# Peripherals.net
KiCad netlist of a schematic drawn in Altium Designer
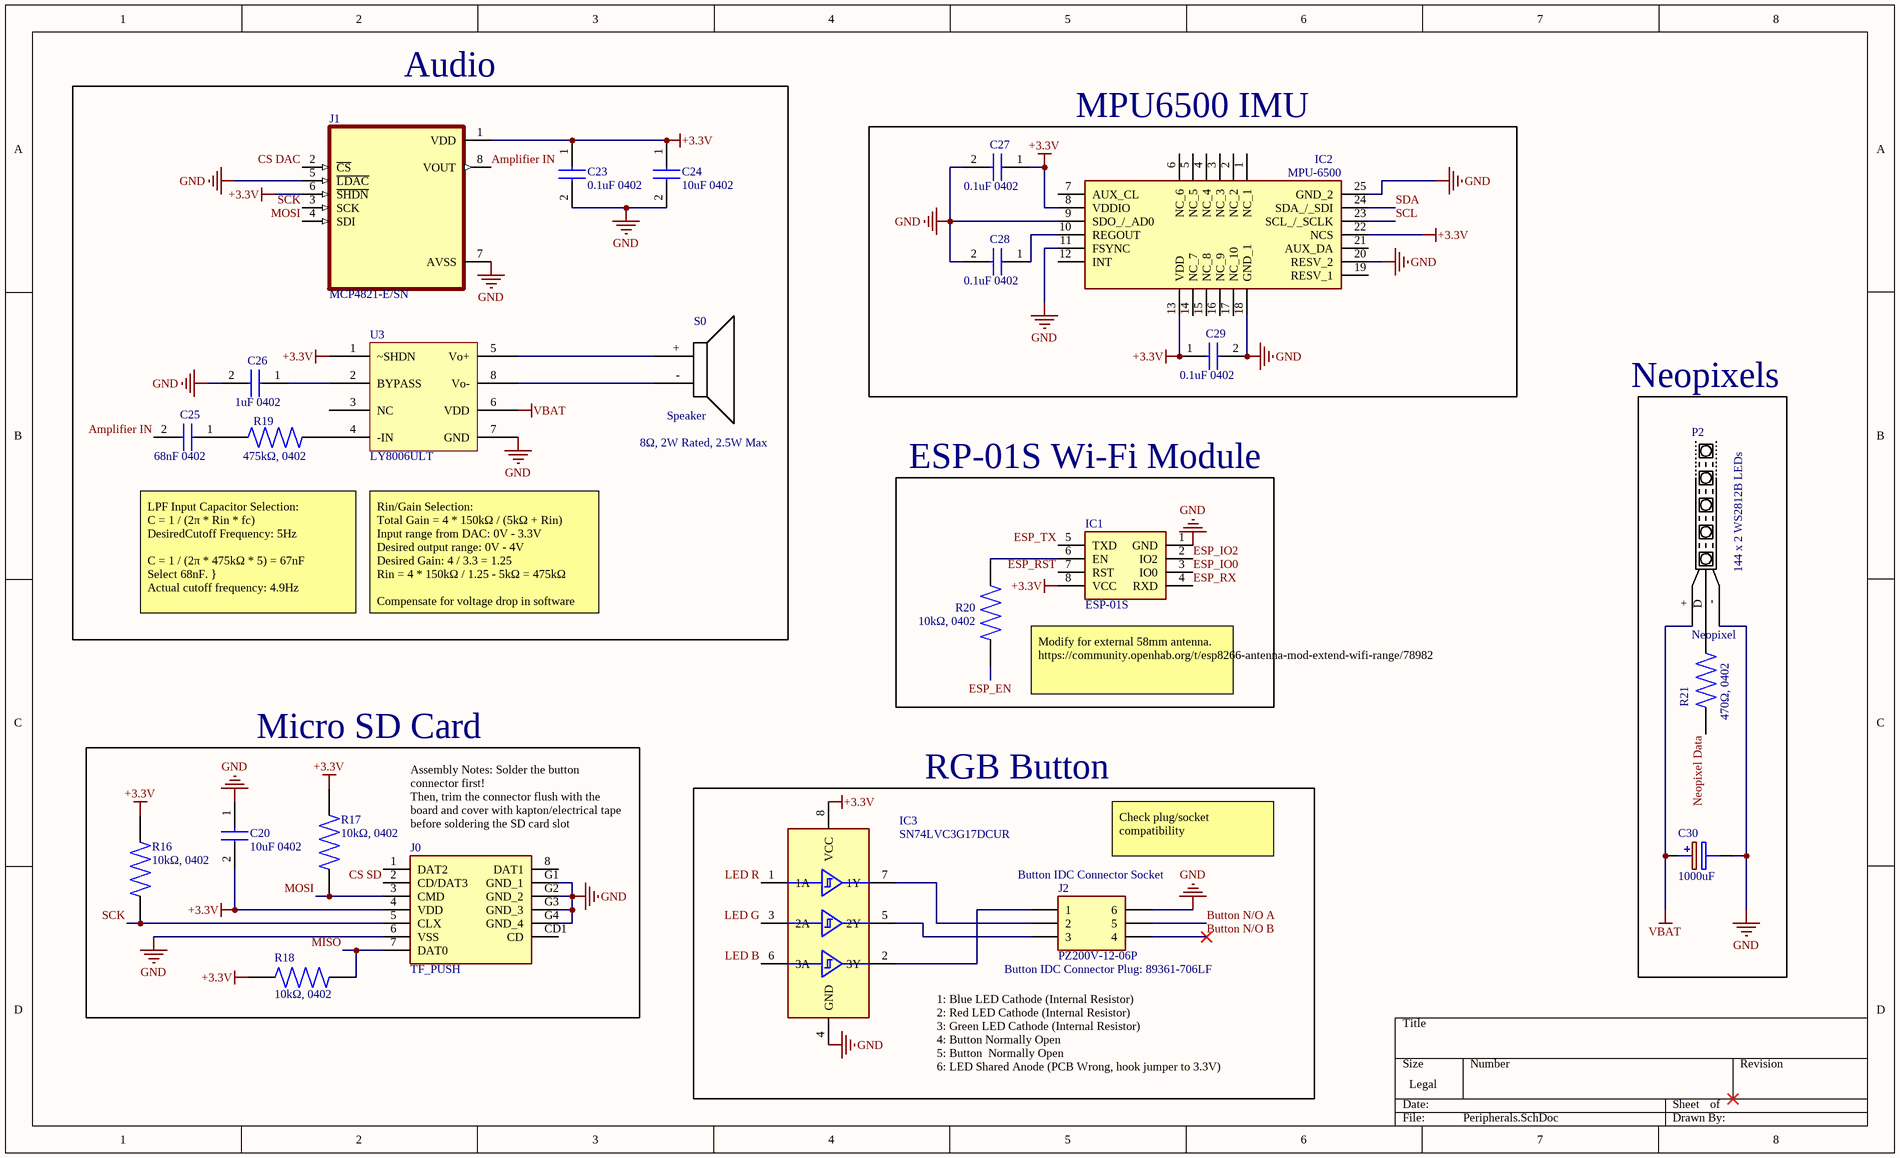
[diagram p0: Peripherals.SchDoc]

(export (version "E")
  (design (tool "Eeschema 10.0.6"))
  (components
    (comp (ref "C20")
      (value "10uF 0402")
      (footprint "SamacSys:CAPC1005X56N")
      (description "Capacitor")
      (fields
        (field (name "MANUFACTURER_PART_NUMBER") "04025A100BAT2A")
        (field (name "MOUSER PART NUMBER") "581-04025A100B")
      )
      (libsource (lib "*") (part "04025A100BAT2A"))
    )
    (comp (ref "C23")
      (value "0.1uF 0402")
      (footprint "SamacSys:CAPC1005X56N")
      (description "Capacitor")
      (fields
        (field (name "MANUFACTURER_PART_NUMBER") "04025A100BAT2A")
        (field (name "MOUSER PART NUMBER") "581-04025A100B")
      )
      (libsource (lib "*") (part "04025A100BAT2A"))
    )
    (comp (ref "C24")
      (value "10uF 0402")
      (footprint "SamacSys:CAPC1005X56N")
      (description "Capacitor")
      (fields
        (field (name "MANUFACTURER_PART_NUMBER") "04025A100BAT2A")
        (field (name "MOUSER PART NUMBER") "581-04025A100B")
      )
      (libsource (lib "*") (part "04025A100BAT2A"))
    )
    (comp (ref "C25")
      (value "68nF 0402")
      (footprint "SamacSys:CAPC1005X56N")
      (description "Capacitor")
      (fields
        (field (name "MANUFACTURER_PART_NUMBER") "04025A100BAT2A")
        (field (name "MOUSER PART NUMBER") "581-04025A100B")
      )
      (libsource (lib "*") (part "04025A100BAT2A"))
    )
    (comp (ref "C26")
      (value "1uF 0402")
      (footprint "SamacSys:CAPC1005X56N")
      (description "Capacitor")
      (fields
        (field (name "MANUFACTURER_PART_NUMBER") "04025A100BAT2A")
        (field (name "MOUSER PART NUMBER") "581-04025A100B")
      )
      (libsource (lib "*") (part "04025A100BAT2A"))
    )
    (comp (ref "C27")
      (value "0.1uF 0402")
      (footprint "SamacSys:CAPC1005X56N")
      (description "Capacitor")
      (fields
        (field (name "MANUFACTURER_PART_NUMBER") "04025A100BAT2A")
        (field (name "MOUSER PART NUMBER") "581-04025A100B")
      )
      (libsource (lib "*") (part "04025A100BAT2A"))
    )
    (comp (ref "C28")
      (value "0.1uF 0402")
      (footprint "SamacSys:CAPC1005X56N")
      (description "Capacitor")
      (fields
        (field (name "MANUFACTURER_PART_NUMBER") "04025A100BAT2A")
        (field (name "MOUSER PART NUMBER") "581-04025A100B")
      )
      (libsource (lib "*") (part "04025A100BAT2A"))
    )
    (comp (ref "C29")
      (value "0.1uF 0402")
      (footprint "SamacSys:CAPC1005X56N")
      (description "Capacitor")
      (fields
        (field (name "MANUFACTURER_PART_NUMBER") "04025A100BAT2A")
        (field (name "MOUSER PART NUMBER") "581-04025A100B")
      )
      (libsource (lib "*") (part "04025A100BAT2A"))
    )
    (comp (ref "C30")
      (value "1000uF")
      (footprint "Lightsaber PCB Library:8x10.2mm Radial Capacitor")
      (description "Capacitor Polarised")
      (fields (field (name "MANUFACTURER_PART_NUMBER") "107CKS035M"))
      (libsource (lib "Lightsaber") (part "8x10.2mm Radial Capacitor"))
    )
    (comp (ref "IC1")
      (value "ESP-01S")
      (footprint "ESP-01")
      (description "Integrated Circuit")
      (fields (field (name "MANUFACTURER_PART_NUMBER") "ESP-01"))
      (libsource (lib "Lightsaber") (part "ESP-01S"))
    )
    (comp (ref "IC2")
      (value "MPU-6500")
      (footprint "QFN-24")
      (description "Integrated Circuit")
      (fields (field (name "MOUSER PART NUMBER") "410-MPU-6500"))
      (libsource (lib "Lightsaber") (part "MPU-6500"))
    )
    (comp (ref "IC3")
      (value "SN74LVC3G17DCUR")
      (footprint "SamacSys:SOP50P310X90-8N")
      (description "Integrated Circuit")
      (fields (field (name "MOUSER PART NUMBER") "595-SN74LVC3G17DCUR"))
      (libsource (lib "*") (part "SN74LVC3G17DCUR"))
    )
    (comp (ref "J0")
      (value "TF_PUSH")
      (footprint "SamacSys:TFPUSH")
      (description "Connector")
      (fields (field (name "MANUFACTURER_PART_NUMBER") "TF PUSH"))
      (libsource (lib "*") (part "TF_PUSH"))
    )
    (comp (ref "J1")
      (value "MCP4821-E/SN")
      (footprint "MCP4821-E_SN:SOIC127P600X175-8N")
      (fields (field (name "MF") "{'manufacturer': u'Microchip'}"))
      (libsource (lib "*") (part "MCP4821-E/SN"))
    )
    (comp (ref "J2")
      (value "PZ200V-12-06P")
      (footprint "2mm 2x3 Header TH")
      (description "Connector")
      (fields
        (field (name "MANUFACTURER_PART_NUMBER") "54202-G08-03")
        (field (name "MOUSER PART NUMBER") "649-54202-G08-03")
      )
      (libsource (lib "Lightsaber") (part "PZ200V-12-06P"))
    )
    (comp (ref "P2")
      (value "Neopixel")
      (footprint "Neopixel Pads")
      (libsource (lib "Lightsaber") (part "Neopixel"))
    )
    (comp (ref "R16")
      (value "10kΩ, 0402")
      (footprint "0402")
      (libsource (lib "Lightsaber") (part "Resistor, 0402"))
    )
    (comp (ref "R17")
      (value "10kΩ, 0402")
      (footprint "0402")
      (libsource (lib "Lightsaber") (part "Resistor, 0402"))
    )
    (comp (ref "R18")
      (value "10kΩ, 0402")
      (footprint "0402")
      (libsource (lib "Lightsaber") (part "Resistor, 0402"))
    )
    (comp (ref "R19")
      (value "475kΩ, 0402")
      (footprint "0402")
      (libsource (lib "Lightsaber") (part "Resistor, 0402"))
    )
    (comp (ref "R20")
      (value "10kΩ, 0402")
      (footprint "0402")
      (libsource (lib "Lightsaber") (part "Resistor, 0402"))
    )
    (comp (ref "R21")
      (value "470Ω, 0402")
      (footprint "0402")
      (libsource (lib "Lightsaber") (part "Resistor, 0402"))
    )
    (comp (ref "S0")
      (value "Speaker")
      (footprint "SPEAKER PADS")
      (libsource (lib "Lightsaber") (part "Speaker"))
    )
    (comp (ref "U3")
      (value "LY8006ULT")
      (footprint "MSOP-8")
      (libsource (lib "Lightsaber") (part "LY8006ULT"))
    )
  )
  (nets
    (net (code "1") (name "+3.3V") (class "Default")
      (node (ref "C20") (pin "2") (pinfunction "2_2") (pintype "passive"))
      (node (ref "C23") (pin "1") (pinfunction "1_1") (pintype "passive"))
      (node (ref "C24") (pin "1") (pinfunction "1_1") (pintype "passive"))
      (node (ref "C27") (pin "1") (pinfunction "1_1") (pintype "passive"))
      (node (ref "C29") (pin "1") (pinfunction "1_1") (pintype "passive"))
      (node (ref "IC1") (pin "8") (pinfunction "VCC_8") (pintype "passive"))
      (node (ref "IC2") (pin "13") (pinfunction "VDD_13") (pintype "passive"))
      (node (ref "IC2") (pin "22") (pinfunction "NCS_22") (pintype "passive"))
      (node (ref "IC2") (pin "8") (pinfunction "VDDIO_8") (pintype "passive"))
      (node (ref "IC3") (pin "8") (pinfunction "VCC_8") (pintype "passive"))
      (node (ref "J0") (pin "4") (pinfunction "VDD_4") (pintype "passive"))
      (node (ref "J1") (pin "1") (pinfunction "VDD_1") (pintype "power_in"))
      (node (ref "J1") (pin "6") (pinfunction "~{SHDN}_6") (pintype "input"))
      (node (ref "R16") (pin "2") (pinfunction "2_2") (pintype "passive"))
      (node (ref "R17") (pin "2") (pinfunction "2_2") (pintype "passive"))
      (node (ref "R18") (pin "2") (pinfunction "2_2") (pintype "passive"))
      (node (ref "U3") (pin "1") (pinfunction "~SHDN_1") (pintype "passive"))
    )
    (net (code "2") (name "/Amplifier IN") (class "Default")
      (node (ref "C25") (pin "2") (pinfunction "2_2") (pintype "passive"))
      (node (ref "J1") (pin "8") (pinfunction "VOUT_8") (pintype "output"))
    )
    (net (code "3") (name "/Button N{slash}O A") (class "Default")
      (node (ref "J2") (pin "5") (pinfunction "5_5") (pintype "passive"))
    )
    (net (code "4") (name "/Button N{slash}O B") (class "Default")
      (node (ref "J2") (pin "4") (pinfunction "4_4") (pintype "passive+no_connect"))
    )
    (net (code "5") (name "/CS DAC") (class "Default")
      (node (ref "J1") (pin "2") (pinfunction "~{CS}_2") (pintype "input"))
    )
    (net (code "6") (name "/CS SD") (class "Default")
      (node (ref "J0") (pin "2") (pinfunction "CD/DAT3_2") (pintype "passive"))
    )
    (net (code "7") (name "/ESP_EN") (class "Default")
      (node (ref "R20") (pin "1") (pinfunction "1_1") (pintype "passive"))
    )
    (net (code "8") (name "/ESP_IO0") (class "Default")
      (node (ref "IC1") (pin "3") (pinfunction "IO0_3") (pintype "passive"))
    )
    (net (code "9") (name "/ESP_IO2") (class "Default")
      (node (ref "IC1") (pin "2") (pinfunction "IO2_2") (pintype "passive"))
    )
    (net (code "10") (name "/ESP_RST") (class "Default")
      (node (ref "IC1") (pin "7") (pinfunction "RST_7") (pintype "passive"))
    )
    (net (code "11") (name "/ESP_RX") (class "Default")
      (node (ref "IC1") (pin "4") (pinfunction "RXD_4") (pintype "passive"))
    )
    (net (code "12") (name "/ESP_TX") (class "Default")
      (node (ref "IC1") (pin "5") (pinfunction "TXD_5") (pintype "passive"))
    )
    (net (code "13") (name "/LED B") (class "Default")
      (node (ref "IC3") (pin "6") (pinfunction "3A_6") (pintype "passive"))
    )
    (net (code "14") (name "/LED G") (class "Default")
      (node (ref "IC3") (pin "3") (pinfunction "2A_3") (pintype "passive"))
    )
    (net (code "15") (name "/LED R") (class "Default")
      (node (ref "IC3") (pin "1") (pinfunction "1A_1") (pintype "passive"))
    )
    (net (code "16") (name "/MISO") (class "Default")
      (node (ref "J0") (pin "7") (pinfunction "DAT0_7") (pintype "passive"))
      (node (ref "R18") (pin "1") (pinfunction "1_1") (pintype "passive"))
    )
    (net (code "17") (name "/MOSI") (class "Default")
      (node (ref "J0") (pin "3") (pinfunction "CMD_3") (pintype "passive"))
      (node (ref "J1") (pin "4") (pinfunction "SDI_4") (pintype "input"))
      (node (ref "R17") (pin "1") (pinfunction "1_1") (pintype "passive"))
    )
    (net (code "18") (name "/Neopixel Data") (class "Default")
      (node (ref "R21") (pin "2") (pinfunction "2_2") (pintype "passive"))
    )
    (net (code "19") (name "/SCK") (class "Default")
      (node (ref "J0") (pin "5") (pinfunction "CLX_5") (pintype "passive"))
      (node (ref "J1") (pin "3") (pinfunction "SCK_3") (pintype "input"))
      (node (ref "R16") (pin "1") (pinfunction "1_1") (pintype "passive"))
    )
    (net (code "20") (name "/SCL") (class "Default")
      (node (ref "IC2") (pin "23") (pinfunction "SCL_/_SCLK_23") (pintype "passive"))
    )
    (net (code "21") (name "/SDA") (class "Default")
      (node (ref "IC2") (pin "24") (pinfunction "SDA_/_SDI_24") (pintype "passive"))
    )
    (net (code "22") (name "GND") (class "Default")
      (node (ref "C20") (pin "1") (pinfunction "1_1") (pintype "passive"))
      (node (ref "C23") (pin "2") (pinfunction "2_2") (pintype "passive"))
      (node (ref "C24") (pin "2") (pinfunction "2_2") (pintype "passive"))
      (node (ref "C26") (pin "2") (pinfunction "2_2") (pintype "passive"))
      (node (ref "C27") (pin "2") (pinfunction "2_2") (pintype "passive"))
      (node (ref "C28") (pin "2") (pinfunction "2_2") (pintype "passive"))
      (node (ref "C29") (pin "2") (pinfunction "2_2") (pintype "passive"))
      (node (ref "C30") (pin "2") (pinfunction "-_2") (pintype "passive"))
      (node (ref "IC1") (pin "1") (pinfunction "GND_1") (pintype "passive"))
      (node (ref "IC2") (pin "11") (pinfunction "FSYNC_11") (pintype "passive"))
      (node (ref "IC2") (pin "18") (pinfunction "GND_1_18") (pintype "passive"))
      (node (ref "IC2") (pin "20") (pinfunction "RESV_2_20") (pintype "passive"))
      (node (ref "IC2") (pin "25") (pinfunction "GND_2_25") (pintype "passive"))
      (node (ref "IC2") (pin "9") (pinfunction "SDO_/_AD0_9") (pintype "passive"))
      (node (ref "IC3") (pin "4") (pinfunction "GND_4") (pintype "passive"))
      (node (ref "J0") (pin "6") (pinfunction "VSS_6") (pintype "passive"))
      (node (ref "J0") (pin "G1") (pinfunction "GND_1_G1") (pintype "passive"))
      (node (ref "J0") (pin "G2") (pinfunction "GND_2_G2") (pintype "passive"))
      (node (ref "J0") (pin "G3") (pinfunction "GND_3_G3") (pintype "passive"))
      (node (ref "J0") (pin "G4") (pinfunction "GND_4_G4") (pintype "passive"))
      (node (ref "J1") (pin "5") (pinfunction "~{LDAC}_5") (pintype "input"))
      (node (ref "J1") (pin "7") (pinfunction "AVSS_7") (pintype "power_in"))
      (node (ref "J2") (pin "6") (pinfunction "6_6") (pintype "passive"))
      (node (ref "P2") (pin "-") (pinfunction "-_-") (pintype "passive"))
      (node (ref "U3") (pin "7") (pinfunction "GND_7") (pintype "passive"))
    )
    (net (code "23") (name "Net-(C25-Pad1)") (class "Default")
      (node (ref "C25") (pin "1") (pinfunction "1_1") (pintype "passive"))
      (node (ref "R19") (pin "1") (pinfunction "1_1") (pintype "passive"))
    )
    (net (code "24") (name "Net-(IC1-EN)") (class "Default")
      (node (ref "IC1") (pin "6") (pinfunction "EN_6") (pintype "passive"))
      (node (ref "R20") (pin "2") (pinfunction "2_2") (pintype "passive"))
    )
    (net (code "25") (name "Net-(IC2-REGOUT)") (class "Default")
      (node (ref "C28") (pin "1") (pinfunction "1_1") (pintype "passive"))
      (node (ref "IC2") (pin "10") (pinfunction "REGOUT_10") (pintype "passive"))
    )
    (net (code "26") (name "Net-(IC3-1Y)") (class "Default")
      (node (ref "IC3") (pin "7") (pinfunction "1Y_7") (pintype "passive"))
      (node (ref "J2") (pin "2") (pinfunction "2_2") (pintype "passive"))
    )
    (net (code "27") (name "Net-(IC3-2Y)") (class "Default")
      (node (ref "IC3") (pin "5") (pinfunction "2Y_5") (pintype "passive"))
      (node (ref "J2") (pin "3") (pinfunction "3_3") (pintype "passive"))
    )
    (net (code "28") (name "Net-(IC3-3Y)") (class "Default")
      (node (ref "IC3") (pin "2") (pinfunction "3Y_2") (pintype "passive"))
      (node (ref "J2") (pin "1") (pinfunction "1_1") (pintype "passive"))
    )
    (net (code "29") (name "Net-(P2-PadD)") (class "Default")
      (node (ref "P2") (pin "D") (pinfunction "D_D") (pintype "passive"))
      (node (ref "R21") (pin "1") (pinfunction "1_1") (pintype "passive"))
    )
    (net (code "30") (name "Net-(U3--IN)") (class "Default")
      (node (ref "R19") (pin "2") (pinfunction "2_2") (pintype "passive"))
      (node (ref "U3") (pin "4") (pinfunction "-IN_4") (pintype "passive"))
    )
    (net (code "31") (name "Net-(U3-BYPASS)") (class "Default")
      (node (ref "C26") (pin "1") (pinfunction "1_1") (pintype "passive"))
      (node (ref "U3") (pin "2") (pinfunction "BYPASS_2") (pintype "passive"))
    )
    (net (code "32") (name "Net-(U3-Vo+)") (class "Default")
      (node (ref "S0") (pin "+") (pintype "passive"))
      (node (ref "U3") (pin "5") (pinfunction "Vo+_5") (pintype "passive"))
    )
    (net (code "33") (name "Net-(U3-Vo-)") (class "Default")
      (node (ref "S0") (pin "-") (pintype "passive"))
      (node (ref "U3") (pin "8") (pinfunction "Vo-_8") (pintype "passive"))
    )
    (net (code "34") (name "VBAT") (class "Default")
      (node (ref "C30") (pin "1") (pinfunction "+_1") (pintype "passive"))
      (node (ref "P2") (pin "+") (pinfunction "+_+") (pintype "passive"))
      (node (ref "U3") (pin "6") (pinfunction "VDD_6") (pintype "passive"))
    )
    (net (code "35") (name "unconnected-(IC2-AUX_CL-Pad7)") (class "Default")
      (node (ref "IC2") (pin "7") (pinfunction "AUX_CL_7") (pintype "passive"))
    )
    (net (code "36") (name "unconnected-(IC2-AUX_DA-Pad21)") (class "Default")
      (node (ref "IC2") (pin "21") (pinfunction "AUX_DA_21") (pintype "passive"))
    )
    (net (code "37") (name "unconnected-(IC2-INT-Pad12)") (class "Default")
      (node (ref "IC2") (pin "12") (pinfunction "INT_12") (pintype "passive"))
    )
    (net (code "38") (name "unconnected-(IC2-NC_1-Pad1)") (class "Default")
      (node (ref "IC2") (pin "1") (pinfunction "NC_1_1") (pintype "passive"))
    )
    (net (code "39") (name "unconnected-(IC2-NC_2-Pad2)") (class "Default")
      (node (ref "IC2") (pin "2") (pinfunction "NC_2_2") (pintype "passive"))
    )
    (net (code "40") (name "unconnected-(IC2-NC_3-Pad3)") (class "Default")
      (node (ref "IC2") (pin "3") (pinfunction "NC_3_3") (pintype "passive"))
    )
    (net (code "41") (name "unconnected-(IC2-NC_4-Pad4)") (class "Default")
      (node (ref "IC2") (pin "4") (pinfunction "NC_4_4") (pintype "passive"))
    )
    (net (code "42") (name "unconnected-(IC2-NC_5-Pad5)") (class "Default")
      (node (ref "IC2") (pin "5") (pinfunction "NC_5_5") (pintype "passive"))
    )
    (net (code "43") (name "unconnected-(IC2-NC_6-Pad6)") (class "Default")
      (node (ref "IC2") (pin "6") (pinfunction "NC_6_6") (pintype "passive"))
    )
    (net (code "44") (name "unconnected-(IC2-NC_7-Pad14)") (class "Default")
      (node (ref "IC2") (pin "14") (pinfunction "NC_7_14") (pintype "passive"))
    )
    (net (code "45") (name "unconnected-(IC2-NC_8-Pad15)") (class "Default")
      (node (ref "IC2") (pin "15") (pinfunction "NC_8_15") (pintype "passive"))
    )
    (net (code "46") (name "unconnected-(IC2-NC_9-Pad16)") (class "Default")
      (node (ref "IC2") (pin "16") (pinfunction "NC_9_16") (pintype "passive"))
    )
    (net (code "47") (name "unconnected-(IC2-NC_10-Pad17)") (class "Default")
      (node (ref "IC2") (pin "17") (pinfunction "NC_10_17") (pintype "passive"))
    )
    (net (code "48") (name "unconnected-(IC2-RESV_1-Pad19)") (class "Default")
      (node (ref "IC2") (pin "19") (pinfunction "RESV_1_19") (pintype "passive"))
    )
    (net (code "49") (name "unconnected-(J0-CD-PadCD1)") (class "Default")
      (node (ref "J0") (pin "CD1") (pinfunction "CD_CD1") (pintype "passive"))
    )
    (net (code "50") (name "unconnected-(J0-DAT1-Pad8)") (class "Default")
      (node (ref "J0") (pin "8") (pinfunction "DAT1_8") (pintype "passive"))
    )
    (net (code "51") (name "unconnected-(J0-DAT2-Pad1)") (class "Default")
      (node (ref "J0") (pin "1") (pinfunction "DAT2_1") (pintype "passive"))
    )
    (net (code "52") (name "unconnected-(U3-NC-Pad3)") (class "Default")
      (node (ref "U3") (pin "3") (pinfunction "NC_3") (pintype "passive"))
    )
  )
)
